# m1-center-plane.net
KiCad netlist of a schematic drawn in EAGLE
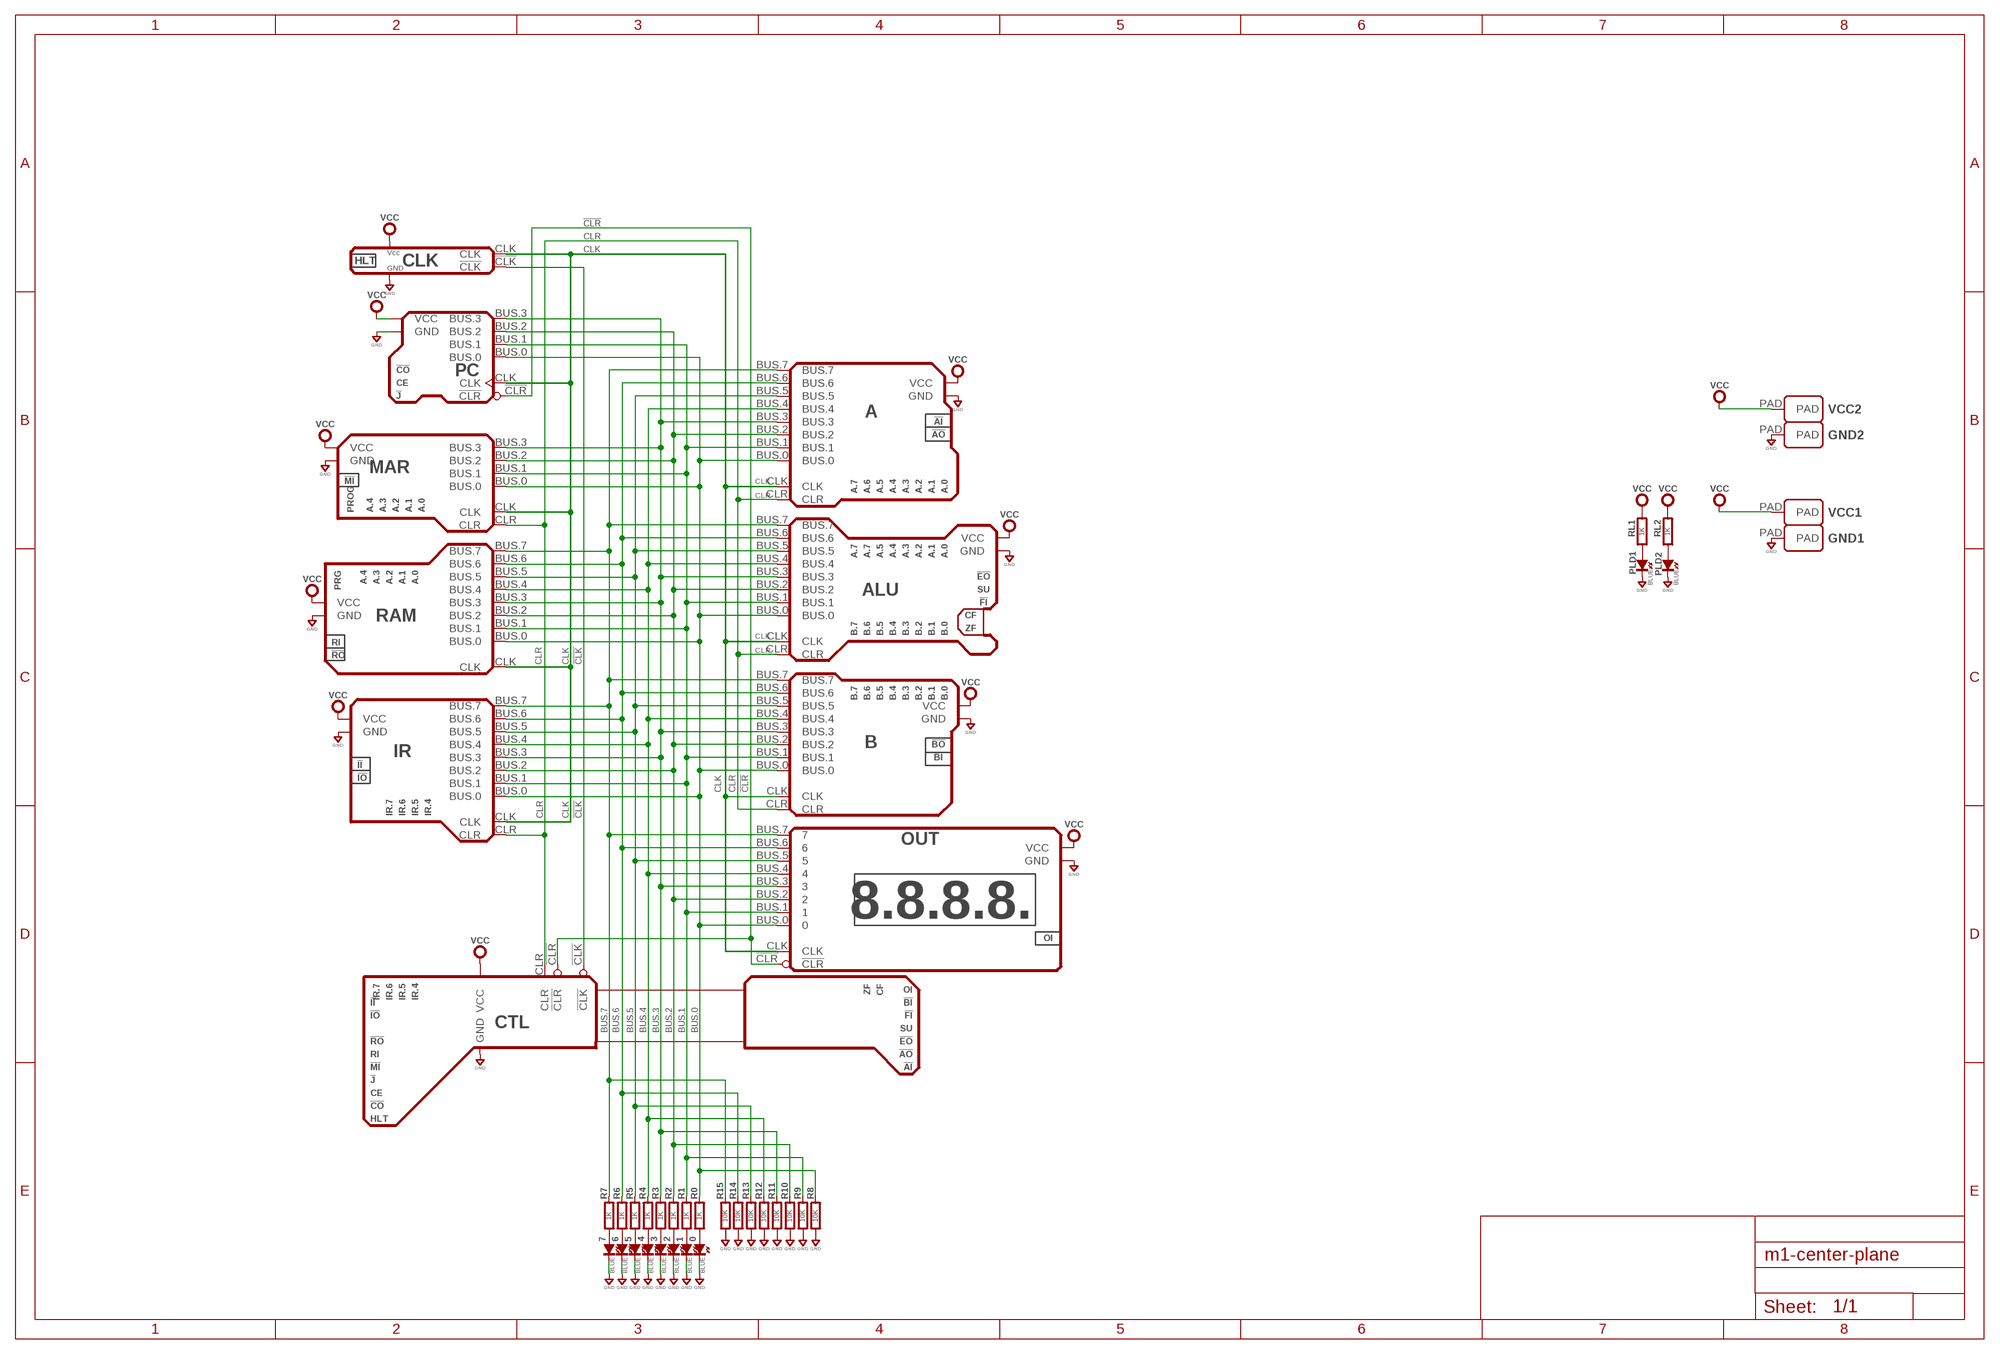
[diagram p0: schematic, sheet 1]

(export (version "E")
  (design (tool "Eeschema 10.0.6"))
  (components
    (comp (ref "0")
      (value "BLUE")
      (footprint "eagle-import:SMD_0603")
      (libsource (lib "eagle-import") (part "SMT0603"))
    )
    (comp (ref "1")
      (value "BLUE")
      (footprint "eagle-import:SMD_0603")
      (libsource (lib "eagle-import") (part "SMT0603"))
    )
    (comp (ref "2")
      (value "BLUE")
      (footprint "eagle-import:SMD_0603")
      (libsource (lib "eagle-import") (part "SMT0603"))
    )
    (comp (ref "3")
      (value "BLUE")
      (footprint "eagle-import:SMD_0603")
      (libsource (lib "eagle-import") (part "SMT0603"))
    )
    (comp (ref "4")
      (value "BLUE")
      (footprint "eagle-import:SMD_0603")
      (libsource (lib "eagle-import") (part "SMT0603"))
    )
    (comp (ref "5")
      (value "BLUE")
      (footprint "eagle-import:SMD_0603")
      (libsource (lib "eagle-import") (part "SMT0603"))
    )
    (comp (ref "6")
      (value "BLUE")
      (footprint "eagle-import:SMD_0603")
      (libsource (lib "eagle-import") (part "SMT0603"))
    )
    (comp (ref "7")
      (value "BLUE")
      (footprint "eagle-import:SMD_0603")
      (libsource (lib "eagle-import") (part "SMT0603"))
    )
    (comp (ref "A")
      (value "M1-REG-A-BUS")
      (footprint "eagle-import:M1-REG-A-BUS")
      (libsource (lib "eagle-import") (part "M1-REG-A-BUS"))
    )
    (comp (ref "ALU")
      (value "M1-ALU-BUS")
      (footprint "eagle-import:M1-ALU-BUS")
      (libsource (lib "eagle-import") (part "M1-ALU-BUS"))
    )
    (comp (ref "B")
      (value "M1-REG-B-BUS")
      (footprint "eagle-import:M1-REG-B-BUS")
      (libsource (lib "eagle-import") (part "M1-REG-B-BUS"))
    )
    (comp (ref "CLK")
      (value "M1-CLOCK-BUS")
      (footprint "eagle-import:M1-CLOCK-BUS")
      (libsource (lib "eagle-import") (part "M1-CLOCK-BUS"))
    )
    (comp (ref "CTL")
      (value "M1-CONTROL-BUS")
      (footprint "eagle-import:M1-CONTROL-BUS")
      (libsource (lib "eagle-import") (part "M1-CONTROL-BUS"))
    )
    (comp (ref "GND1")
      (value "PADSMD-100X100")
      (footprint "eagle-import:SMD-100X100")
      (libsource (lib "eagle-import") (part "PADSMD-100X100"))
    )
    (comp (ref "GND2")
      (value "PADSMD-100X100")
      (footprint "eagle-import:SMD-100X100")
      (libsource (lib "eagle-import") (part "PADSMD-100X100"))
    )
    (comp (ref "IR")
      (value "M1-REG-INSTR-BUS")
      (footprint "eagle-import:M1-REG-I-BUS")
      (libsource (lib "eagle-import") (part "M1-REG-INSTR-BUS"))
    )
    (comp (ref "MAR")
      (value "M1-MAR-BUS")
      (footprint "eagle-import:M1-MAR-BUS")
      (libsource (lib "eagle-import") (part "M1-MAR-BUS"))
    )
    (comp (ref "OUT")
      (value "M1-REG-OUTPUT-BUS")
      (footprint "eagle-import:M1-REG-OUTPUT-BUS")
      (libsource (lib "eagle-import") (part "M1-REG-OUTPUT-BUS"))
    )
    (comp (ref "PC")
      (value "M1-PROG-COUNTER-BUS")
      (footprint "eagle-import:M1-PROGRAM-COUNTER-BUS")
      (libsource (lib "eagle-import") (part "M1-PROG-COUNTER-BUS"))
    )
    (comp (ref "PLD1")
      (value "BLUE")
      (footprint "eagle-import:SMD_0603")
      (libsource (lib "eagle-import") (part "SMT0603"))
    )
    (comp (ref "PLD2")
      (value "BLUE")
      (footprint "eagle-import:SMD_0603")
      (libsource (lib "eagle-import") (part "SMT0603"))
    )
    (comp (ref "R0")
      (value "1K")
      (footprint "eagle-import:0603-RES")
      (libsource (lib "eagle-import") (part "RESISTOR0603"))
    )
    (comp (ref "R1")
      (value "1K")
      (footprint "eagle-import:0603-RES")
      (libsource (lib "eagle-import") (part "RESISTOR0603"))
    )
    (comp (ref "R2")
      (value "1K")
      (footprint "eagle-import:0603-RES")
      (libsource (lib "eagle-import") (part "RESISTOR0603"))
    )
    (comp (ref "R3")
      (value "1K")
      (footprint "eagle-import:0603-RES")
      (libsource (lib "eagle-import") (part "RESISTOR0603"))
    )
    (comp (ref "R4")
      (value "1K")
      (footprint "eagle-import:0603-RES")
      (libsource (lib "eagle-import") (part "RESISTOR0603"))
    )
    (comp (ref "R5")
      (value "1K")
      (footprint "eagle-import:0603-RES")
      (libsource (lib "eagle-import") (part "RESISTOR0603"))
    )
    (comp (ref "R6")
      (value "1K")
      (footprint "eagle-import:0603-RES")
      (libsource (lib "eagle-import") (part "RESISTOR0603"))
    )
    (comp (ref "R7")
      (value "1K")
      (footprint "eagle-import:0603-RES")
      (libsource (lib "eagle-import") (part "RESISTOR0603"))
    )
    (comp (ref "R8")
      (value "10K")
      (footprint "eagle-import:0603-RES")
      (libsource (lib "eagle-import") (part "RESISTOR0603"))
    )
    (comp (ref "R9")
      (value "10K")
      (footprint "eagle-import:0603-RES")
      (libsource (lib "eagle-import") (part "RESISTOR0603"))
    )
    (comp (ref "R10")
      (value "10K")
      (footprint "eagle-import:0603-RES")
      (libsource (lib "eagle-import") (part "RESISTOR0603"))
    )
    (comp (ref "R11")
      (value "10K")
      (footprint "eagle-import:0603-RES")
      (libsource (lib "eagle-import") (part "RESISTOR0603"))
    )
    (comp (ref "R12")
      (value "10K")
      (footprint "eagle-import:0603-RES")
      (libsource (lib "eagle-import") (part "RESISTOR0603"))
    )
    (comp (ref "R13")
      (value "10K")
      (footprint "eagle-import:0603-RES")
      (libsource (lib "eagle-import") (part "RESISTOR0603"))
    )
    (comp (ref "R14")
      (value "10K")
      (footprint "eagle-import:0603-RES")
      (libsource (lib "eagle-import") (part "RESISTOR0603"))
    )
    (comp (ref "R15")
      (value "10K")
      (footprint "eagle-import:0603-RES")
      (libsource (lib "eagle-import") (part "RESISTOR0603"))
    )
    (comp (ref "RAM")
      (value "M1-RAM-BUS")
      (footprint "eagle-import:M1-RAM-BUS")
      (libsource (lib "eagle-import") (part "M1-RAM-BUS"))
    )
    (comp (ref "RL1")
      (value "1K")
      (footprint "eagle-import:0603-RES")
      (libsource (lib "eagle-import") (part "RESISTOR0603"))
    )
    (comp (ref "RL2")
      (value "1K")
      (footprint "eagle-import:0603-RES")
      (libsource (lib "eagle-import") (part "RESISTOR0603"))
    )
    (comp (ref "VCC1")
      (value "PADSMD-100X100")
      (footprint "eagle-import:SMD-100X100")
      (libsource (lib "eagle-import") (part "PADSMD-100X100"))
    )
    (comp (ref "VCC2")
      (value "PADSMD-100X100")
      (footprint "eagle-import:SMD-100X100")
      (libsource (lib "eagle-import") (part "PADSMD-100X100"))
    )
  )
  (nets
    (net (code "1") (name "/BUS.0") (class "Default")
      (node (ref "A") (pin "BUS.0") (pinfunction "BUS.0_BUS.0") (pintype "input"))
      (node (ref "ALU") (pin "BUS.0") (pinfunction "BUS.0_BUS.0") (pintype "input"))
      (node (ref "B") (pin "BUS.0") (pinfunction "BUS.0_BUS.0") (pintype "input"))
      (node (ref "IR") (pin "BUS.0") (pinfunction "BUS.0_BUS.0") (pintype "input"))
      (node (ref "MAR") (pin "BUS.0") (pinfunction "BUS.0_BUS.0") (pintype "input"))
      (node (ref "OUT") (pin "BUS.0") (pinfunction "0_BUS.0") (pintype "output"))
      (node (ref "PC") (pin "BUS.0") (pinfunction "BUS.0_BUS.0") (pintype "input"))
      (node (ref "R0") (pin "2") (pinfunction "2_2") (pintype "passive"))
      (node (ref "R8") (pin "2") (pinfunction "2_2") (pintype "passive"))
      (node (ref "RAM") (pin "BUS.0") (pinfunction "BUS.0_BUS.0") (pintype "input"))
    )
    (net (code "2") (name "/BUS.1") (class "Default")
      (node (ref "A") (pin "BUS.1") (pinfunction "BUS.1_BUS.1") (pintype "input"))
      (node (ref "ALU") (pin "BUS.1") (pinfunction "BUS.1_BUS.1") (pintype "input"))
      (node (ref "B") (pin "BUS.1") (pinfunction "BUS.1_BUS.1") (pintype "input"))
      (node (ref "IR") (pin "BUS.1") (pinfunction "BUS.1_BUS.1") (pintype "input"))
      (node (ref "MAR") (pin "BUS.1") (pinfunction "BUS.1_BUS.1") (pintype "input"))
      (node (ref "OUT") (pin "BUS.1") (pinfunction "1_BUS.1") (pintype "output"))
      (node (ref "PC") (pin "BUS.1") (pinfunction "BUS.1_BUS.1") (pintype "input"))
      (node (ref "R1") (pin "2") (pinfunction "2_2") (pintype "passive"))
      (node (ref "R9") (pin "2") (pinfunction "2_2") (pintype "passive"))
      (node (ref "RAM") (pin "BUS.1") (pinfunction "BUS.1_BUS.1") (pintype "input"))
    )
    (net (code "3") (name "/BUS.2") (class "Default")
      (node (ref "A") (pin "BUS.2") (pinfunction "BUS.2_BUS.2") (pintype "input"))
      (node (ref "ALU") (pin "BUS.2") (pinfunction "BUS.2_BUS.2") (pintype "input"))
      (node (ref "B") (pin "BUS.2") (pinfunction "BUS.2_BUS.2") (pintype "input"))
      (node (ref "IR") (pin "BUS.2") (pinfunction "BUS.2_BUS.2") (pintype "input"))
      (node (ref "MAR") (pin "BUS.2") (pinfunction "BUS.2_BUS.2") (pintype "input"))
      (node (ref "OUT") (pin "BUS.2") (pinfunction "2_BUS.2") (pintype "output"))
      (node (ref "PC") (pin "BUS.2") (pinfunction "BUS.2_BUS.2") (pintype "input"))
      (node (ref "R10") (pin "2") (pinfunction "2_2") (pintype "passive"))
      (node (ref "R2") (pin "2") (pinfunction "2_2") (pintype "passive"))
      (node (ref "RAM") (pin "BUS.2") (pinfunction "BUS.2_BUS.2") (pintype "input"))
    )
    (net (code "4") (name "/BUS.3") (class "Default")
      (node (ref "A") (pin "BUS.3") (pinfunction "BUS.3_BUS.3") (pintype "input"))
      (node (ref "ALU") (pin "BUS.3") (pinfunction "BUS.3_BUS.3") (pintype "input"))
      (node (ref "B") (pin "BUS.3") (pinfunction "BUS.3_BUS.3") (pintype "input"))
      (node (ref "IR") (pin "BUS.3") (pinfunction "BUS.3_BUS.3") (pintype "input"))
      (node (ref "MAR") (pin "BUS.3") (pinfunction "BUS.3_BUS.3") (pintype "input"))
      (node (ref "OUT") (pin "BUS.3") (pinfunction "3_BUS.3") (pintype "output"))
      (node (ref "PC") (pin "BUS.3") (pinfunction "BUS.3_BUS.3") (pintype "input"))
      (node (ref "R11") (pin "2") (pinfunction "2_2") (pintype "passive"))
      (node (ref "R3") (pin "2") (pinfunction "2_2") (pintype "passive"))
      (node (ref "RAM") (pin "BUS.3") (pinfunction "BUS.3_BUS.3") (pintype "input"))
    )
    (net (code "5") (name "/BUS.4") (class "Default")
      (node (ref "A") (pin "BUS.4") (pinfunction "BUS.4_BUS.4") (pintype "input"))
      (node (ref "ALU") (pin "BUS.4") (pinfunction "BUS.4_BUS.4") (pintype "input"))
      (node (ref "B") (pin "BUS.4") (pinfunction "BUS.4_BUS.4") (pintype "input"))
      (node (ref "IR") (pin "BUS.4") (pinfunction "BUS.4_BUS.4") (pintype "input"))
      (node (ref "OUT") (pin "BUS.4") (pinfunction "4_BUS.4") (pintype "output"))
      (node (ref "R12") (pin "2") (pinfunction "2_2") (pintype "passive"))
      (node (ref "R4") (pin "2") (pinfunction "2_2") (pintype "passive"))
      (node (ref "RAM") (pin "BUS.4") (pinfunction "BUS.4_BUS.4") (pintype "input"))
    )
    (net (code "6") (name "/BUS.5") (class "Default")
      (node (ref "A") (pin "BUS.5") (pinfunction "BUS.5_BUS.5") (pintype "input"))
      (node (ref "ALU") (pin "BUS.5") (pinfunction "BUS.5_BUS.5") (pintype "input"))
      (node (ref "B") (pin "BUS.5") (pinfunction "BUS.5_BUS.5") (pintype "input"))
      (node (ref "IR") (pin "BUS.5") (pinfunction "BUS.5_BUS.5") (pintype "input"))
      (node (ref "OUT") (pin "BUS.5") (pinfunction "5_BUS.5") (pintype "output"))
      (node (ref "R13") (pin "2") (pinfunction "2_2") (pintype "passive"))
      (node (ref "R5") (pin "2") (pinfunction "2_2") (pintype "passive"))
      (node (ref "RAM") (pin "BUS.5") (pinfunction "BUS.5_BUS.5") (pintype "input"))
    )
    (net (code "7") (name "/BUS.6") (class "Default")
      (node (ref "A") (pin "BUS.6") (pinfunction "BUS.6_BUS.6") (pintype "input"))
      (node (ref "ALU") (pin "BUS.6") (pinfunction "BUS.6_BUS.6") (pintype "input"))
      (node (ref "B") (pin "BUS.6") (pinfunction "BUS.6_BUS.6") (pintype "input"))
      (node (ref "IR") (pin "BUS.6") (pinfunction "BUS.6_BUS.6") (pintype "input"))
      (node (ref "OUT") (pin "BUS.6") (pinfunction "6_BUS.6") (pintype "output"))
      (node (ref "R14") (pin "2") (pinfunction "2_2") (pintype "passive"))
      (node (ref "R6") (pin "2") (pinfunction "2_2") (pintype "passive"))
      (node (ref "RAM") (pin "BUS.6") (pinfunction "BUS.6_BUS.6") (pintype "input"))
    )
    (net (code "8") (name "/BUS.7") (class "Default")
      (node (ref "A") (pin "BUS.7") (pinfunction "BUS.7_BUS.7") (pintype "input"))
      (node (ref "ALU") (pin "BUS.7") (pinfunction "BUS.7_BUS.7") (pintype "input"))
      (node (ref "B") (pin "BUS.7") (pinfunction "BUS.7_BUS.7") (pintype "input"))
      (node (ref "IR") (pin "BUS.7") (pinfunction "BUS.7_BUS.7") (pintype "input"))
      (node (ref "OUT") (pin "BUS.7") (pinfunction "7_BUS.7") (pintype "output"))
      (node (ref "R15") (pin "2") (pinfunction "2_2") (pintype "passive"))
      (node (ref "R7") (pin "2") (pinfunction "2_2") (pintype "passive"))
      (node (ref "RAM") (pin "BUS.7") (pinfunction "BUS.7_BUS.7") (pintype "input"))
    )
    (net (code "9") (name "/CLK") (class "Default")
      (node (ref "A") (pin "CLK") (pinfunction "CLK_CLK") (pintype "input"))
      (node (ref "ALU") (pin "CLK") (pinfunction "CLK_CLK") (pintype "input"))
      (node (ref "B") (pin "CLK") (pinfunction "CLK_CLK") (pintype "input"))
      (node (ref "CLK") (pin "CLK") (pinfunction "CLK_CLK") (pintype "output"))
      (node (ref "IR") (pin "CLK") (pinfunction "CLK_CLK") (pintype "input"))
      (node (ref "MAR") (pin "CLK") (pinfunction "CLK_CLK") (pintype "input"))
      (node (ref "OUT") (pin "CLK") (pinfunction "CLK_CLK") (pintype "input"))
      (node (ref "PC") (pin "CLK") (pinfunction "CLK_CLK") (pintype "input"))
      (node (ref "RAM") (pin "CLK") (pinfunction "CLK_CLK") (pintype "input"))
    )
    (net (code "10") (name "/CLR") (class "Default")
      (node (ref "A") (pin "CLR") (pinfunction "CLR_CLR") (pintype "input"))
      (node (ref "ALU") (pin "CLR") (pinfunction "CLR_CLR") (pintype "input"))
      (node (ref "B") (pin "CLR") (pinfunction "CLR_CLR") (pintype "input"))
      (node (ref "CTL") (pin "CLR") (pinfunction "CLR_CLR") (pintype "bidirectional"))
      (node (ref "IR") (pin "CLR") (pinfunction "CLR_CLR") (pintype "input"))
      (node (ref "MAR") (pin "CLR") (pinfunction "CLR_CLR") (pintype "input"))
    )
    (net (code "11") (name "/~{CLK}") (class "Default")
      (node (ref "CLK") (pin "!CLK") (pinfunction "~{CLK}_!CLK") (pintype "output"))
      (node (ref "CTL") (pin "!CLK") (pinfunction "~{CLK}_!CLK") (pintype "bidirectional"))
    )
    (net (code "12") (name "/~{CLR}") (class "Default")
      (node (ref "CTL") (pin "!CLR") (pinfunction "~{CLR}_!CLR") (pintype "bidirectional"))
      (node (ref "OUT") (pin "!CLR") (pinfunction "~{CLR}_!CLR") (pintype "input"))
      (node (ref "PC") (pin "!CLR") (pinfunction "~{CLR}_!CLR") (pintype "input"))
    )
    (net (code "13") (name "GND") (class "Default")
      (node (ref "0") (pin "K") (pinfunction "C_K") (pintype "passive"))
      (node (ref "1") (pin "K") (pinfunction "C_K") (pintype "passive"))
      (node (ref "2") (pin "K") (pinfunction "C_K") (pintype "passive"))
      (node (ref "3") (pin "K") (pinfunction "C_K") (pintype "passive"))
      (node (ref "4") (pin "K") (pinfunction "C_K") (pintype "passive"))
      (node (ref "5") (pin "K") (pinfunction "C_K") (pintype "passive"))
      (node (ref "6") (pin "K") (pinfunction "C_K") (pintype "passive"))
      (node (ref "7") (pin "K") (pinfunction "C_K") (pintype "passive"))
      (node (ref "A") (pin "GND") (pinfunction "GND_GND") (pintype "power_in"))
      (node (ref "ALU") (pin "GND") (pinfunction "GND_GND") (pintype "power_in"))
      (node (ref "B") (pin "GND") (pinfunction "GND_GND") (pintype "power_in"))
      (node (ref "CLK") (pin "GND") (pinfunction "GND_GND") (pintype "power_in"))
      (node (ref "CTL") (pin "GND") (pinfunction "GND_GND") (pintype "power_in"))
      (node (ref "GND1") (pin "PAD") (pinfunction "PAD_PAD") (pintype "bidirectional"))
      (node (ref "GND2") (pin "PAD") (pinfunction "PAD_PAD") (pintype "bidirectional"))
      (node (ref "IR") (pin "GND") (pinfunction "GND_GND") (pintype "power_in"))
      (node (ref "MAR") (pin "GND") (pinfunction "GND_GND") (pintype "power_in"))
      (node (ref "OUT") (pin "GND") (pinfunction "GND_GND") (pintype "power_in"))
      (node (ref "PC") (pin "GND") (pinfunction "GND_GND") (pintype "power_in"))
      (node (ref "PLD1") (pin "K") (pinfunction "C_K") (pintype "passive"))
      (node (ref "PLD2") (pin "K") (pinfunction "C_K") (pintype "passive"))
      (node (ref "R10") (pin "1") (pinfunction "1_1") (pintype "passive"))
      (node (ref "R11") (pin "1") (pinfunction "1_1") (pintype "passive"))
      (node (ref "R12") (pin "1") (pinfunction "1_1") (pintype "passive"))
      (node (ref "R13") (pin "1") (pinfunction "1_1") (pintype "passive"))
      (node (ref "R14") (pin "1") (pinfunction "1_1") (pintype "passive"))
      (node (ref "R15") (pin "1") (pinfunction "1_1") (pintype "passive"))
      (node (ref "R8") (pin "1") (pinfunction "1_1") (pintype "passive"))
      (node (ref "R9") (pin "1") (pinfunction "1_1") (pintype "passive"))
      (node (ref "RAM") (pin "GND") (pinfunction "GND_GND") (pintype "power_in"))
    )
    (net (code "14") (name "Net-(0-PadA)") (class "Default")
      (node (ref "0") (pin "A") (pinfunction "A_A") (pintype "passive"))
      (node (ref "R0") (pin "1") (pinfunction "1_1") (pintype "passive"))
    )
    (net (code "15") (name "Net-(1-PadA)") (class "Default")
      (node (ref "1") (pin "A") (pinfunction "A_A") (pintype "passive"))
      (node (ref "R1") (pin "1") (pinfunction "1_1") (pintype "passive"))
    )
    (net (code "16") (name "Net-(2-PadA)") (class "Default")
      (node (ref "2") (pin "A") (pinfunction "A_A") (pintype "passive"))
      (node (ref "R2") (pin "1") (pinfunction "1_1") (pintype "passive"))
    )
    (net (code "17") (name "Net-(3-PadA)") (class "Default")
      (node (ref "3") (pin "A") (pinfunction "A_A") (pintype "passive"))
      (node (ref "R3") (pin "1") (pinfunction "1_1") (pintype "passive"))
    )
    (net (code "18") (name "Net-(4-PadA)") (class "Default")
      (node (ref "4") (pin "A") (pinfunction "A_A") (pintype "passive"))
      (node (ref "R4") (pin "1") (pinfunction "1_1") (pintype "passive"))
    )
    (net (code "19") (name "Net-(5-PadA)") (class "Default")
      (node (ref "5") (pin "A") (pinfunction "A_A") (pintype "passive"))
      (node (ref "R5") (pin "1") (pinfunction "1_1") (pintype "passive"))
    )
    (net (code "20") (name "Net-(6-PadA)") (class "Default")
      (node (ref "6") (pin "A") (pinfunction "A_A") (pintype "passive"))
      (node (ref "R6") (pin "1") (pinfunction "1_1") (pintype "passive"))
    )
    (net (code "21") (name "Net-(7-PadA)") (class "Default")
      (node (ref "7") (pin "A") (pinfunction "A_A") (pintype "passive"))
      (node (ref "R7") (pin "1") (pinfunction "1_1") (pintype "passive"))
    )
    (net (code "22") (name "Net-(PLD1-PadA)") (class "Default")
      (node (ref "PLD1") (pin "A") (pinfunction "A_A") (pintype "passive"))
      (node (ref "RL1") (pin "1") (pinfunction "1_1") (pintype "passive"))
    )
    (net (code "23") (name "Net-(PLD2-PadA)") (class "Default")
      (node (ref "PLD2") (pin "A") (pinfunction "A_A") (pintype "passive"))
      (node (ref "RL2") (pin "1") (pinfunction "1_1") (pintype "passive"))
    )
    (net (code "24") (name "VCC") (class "Default")
      (node (ref "A") (pin "VCC") (pinfunction "VCC_VCC") (pintype "power_in"))
      (node (ref "ALU") (pin "VCC") (pinfunction "VCC_VCC") (pintype "power_in"))
      (node (ref "B") (pin "VCC") (pinfunction "VCC_VCC") (pintype "power_in"))
      (node (ref "CLK") (pin "VCC") (pinfunction "VCC_VCC") (pintype "power_in"))
      (node (ref "CTL") (pin "VCC") (pinfunction "VCC_VCC") (pintype "power_in"))
      (node (ref "IR") (pin "VCC") (pinfunction "VCC_VCC") (pintype "power_in"))
      (node (ref "MAR") (pin "VCC") (pinfunction "VCC_VCC") (pintype "power_in"))
      (node (ref "OUT") (pin "VCC") (pinfunction "VCC_VCC") (pintype "power_in"))
      (node (ref "PC") (pin "VCC") (pinfunction "VCC_VCC") (pintype "power_in"))
      (node (ref "RAM") (pin "VCC") (pinfunction "VCC_VCC") (pintype "power_in"))
      (node (ref "RL1") (pin "2") (pinfunction "2_2") (pintype "passive"))
      (node (ref "RL2") (pin "2") (pinfunction "2_2") (pintype "passive"))
      (node (ref "VCC1") (pin "PAD") (pinfunction "PAD_PAD") (pintype "bidirectional"))
      (node (ref "VCC2") (pin "PAD") (pinfunction "PAD_PAD") (pintype "bidirectional"))
    )
  )
)
